# hiveScale.net
KiCad netlist of a schematic drawn in EAGLE
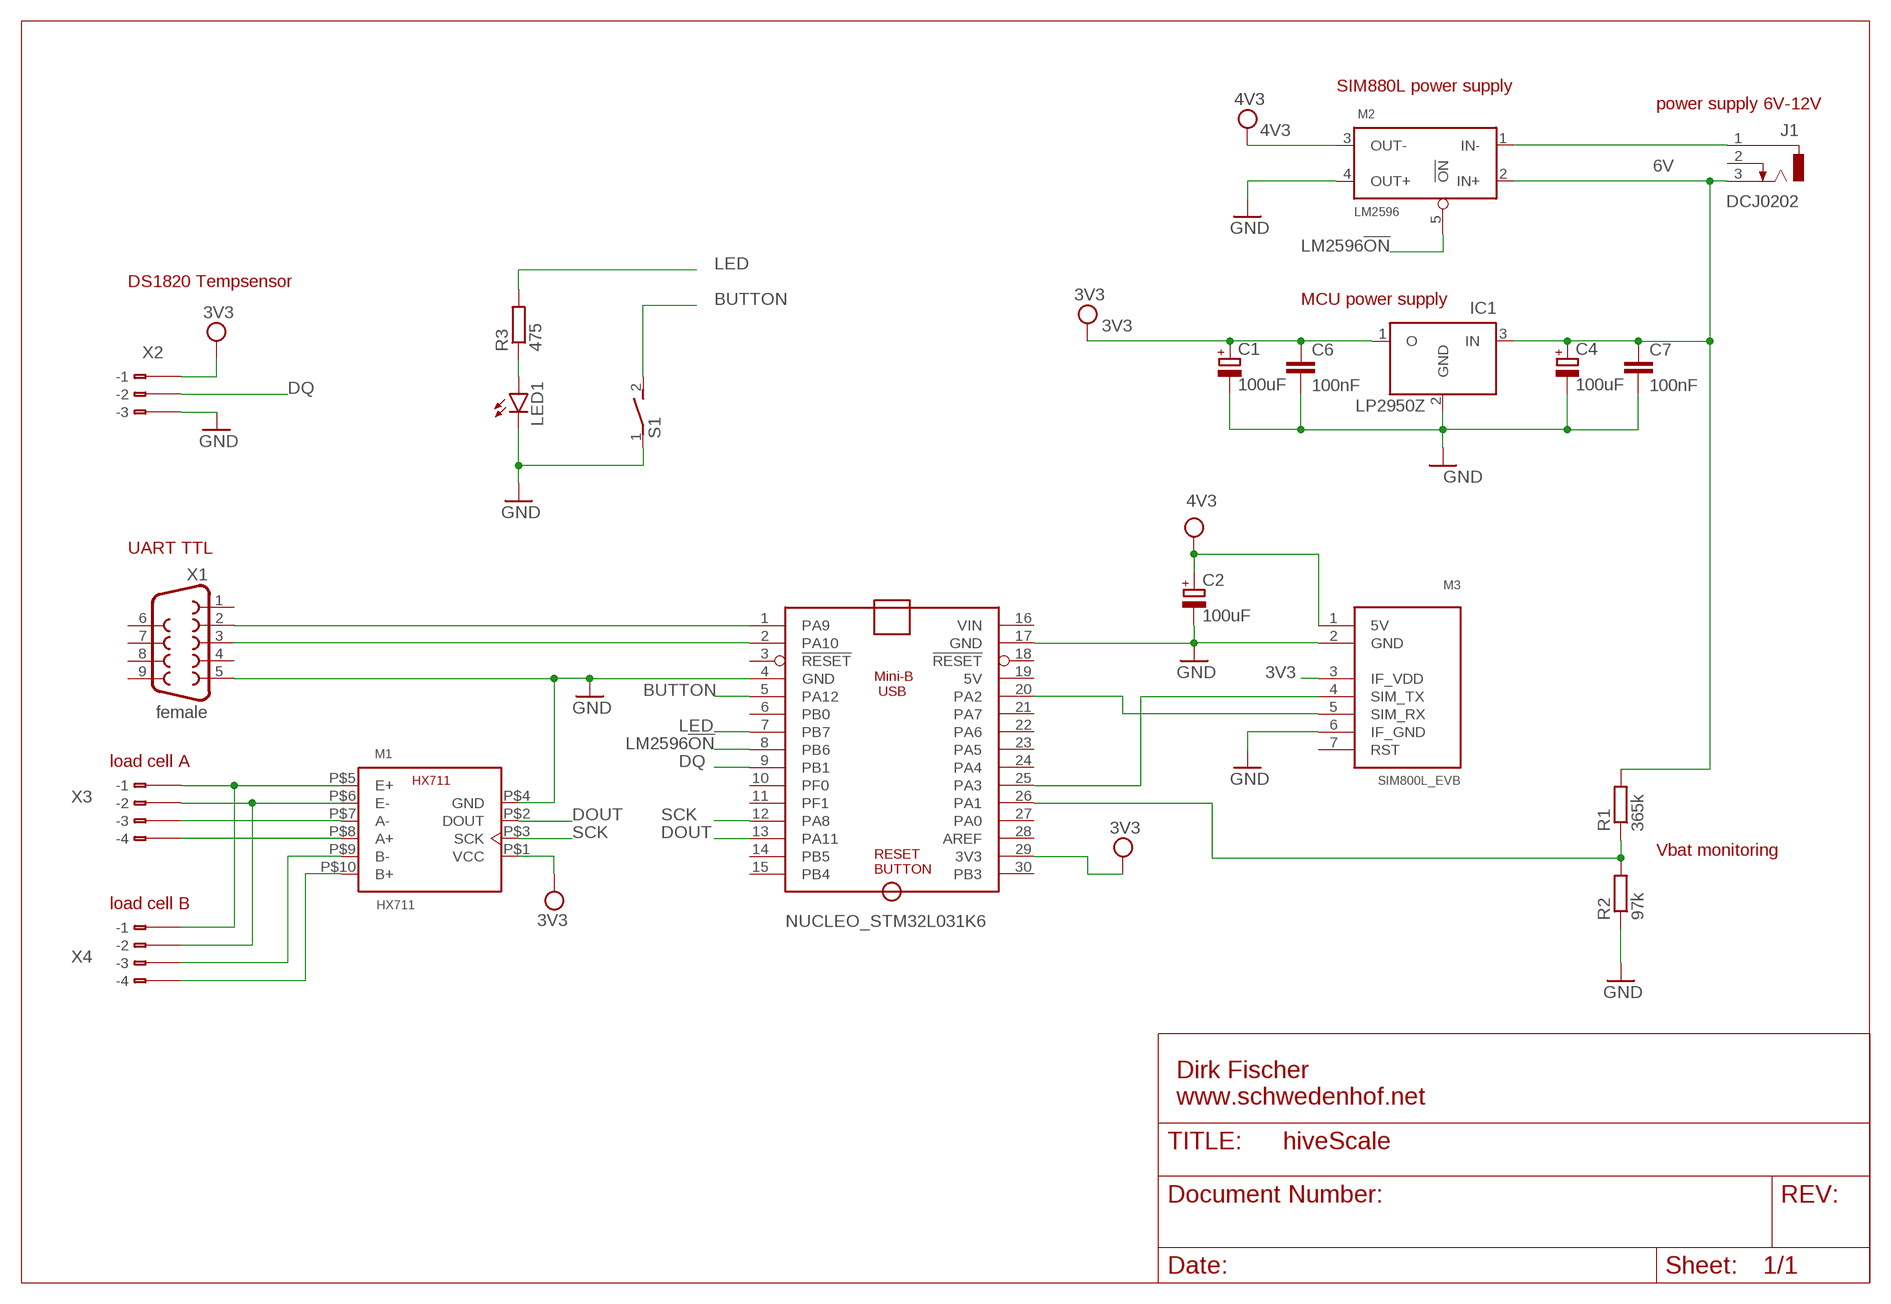
[diagram p0: schematic, sheet 1]

(export (version "E")
  (design (tool "Eeschema 10.0.6"))
  (components
    (comp (ref "C1")
      (value "100uF")
      (footprint "eagle-import:085CS_1AR")
      (libsource (lib "eagle-import") (part "CPOL-EU085CS-1AR"))
    )
    (comp (ref "C2")
      (value "100uF")
      (footprint "eagle-import:085CS_1AR")
      (libsource (lib "eagle-import") (part "CPOL-EU085CS-1AR"))
    )
    (comp (ref "C4")
      (value "100uF")
      (footprint "eagle-import:085CS_1AR")
      (libsource (lib "eagle-import") (part "CPOL-EU085CS-1AR"))
    )
    (comp (ref "C6")
      (value "100nF")
      (footprint "eagle-import:C025-024X044")
      (libsource (lib "eagle-import") (part "C-EU025-024X044"))
    )
    (comp (ref "C7")
      (value "100nF")
      (footprint "eagle-import:C025-024X044")
      (libsource (lib "eagle-import") (part "C-EU025-024X044"))
    )
    (comp (ref "IC1")
      (value "LP2950Z")
      (footprint "eagle-import:TO92")
      (fields (field (name "MF") "NATIONAL SEMICONDUCTOR") (field (name "MPN") "LP2950CZ-5.0/NOPB"))
      (libsource (lib "eagle-import") (part "LP2950Z"))
    )
    (comp (ref "J1")
      (value "DCJ0202")
      (footprint "eagle-import:DCJ0202")
      (libsource (lib "eagle-import") (part "DCJ0202"))
    )
    (comp (ref "LED1")
      (value "LED5MM")
      (footprint "eagle-import:LED5MM")
      (libsource (lib "eagle-import") (part "LED5MM"))
    )
    (comp (ref "M1")
      (value "HX711")
      (footprint "eagle-import:HX711")
      (libsource (lib "eagle-import") (part "HX711"))
    )
    (comp (ref "M2")
      (value "LM2596")
      (footprint "eagle-import:LM2596")
      (libsource (lib "eagle-import") (part "LM2596"))
    )
    (comp (ref "M3")
      (value "SIM800L_EVB")
      (footprint "eagle-import:SIM800L_EVB")
      (libsource (lib "eagle-import") (part "hiveScale_SIM800L_EVB"))
    )
    (comp (ref "NUCLEO_STM32L031K6")
      (value "ARDUINO_NANO")
      (footprint "eagle-import:ARDUINO_NANO")
      (libsource (lib "eagle-import") (part "ARDUINO_NANO"))
    )
    (comp (ref "R1")
      (value "365k")
      (footprint "eagle-import:0204_7")
      (libsource (lib "eagle-import") (part "R-EU_0204/7"))
    )
    (comp (ref "R2")
      (value "97k")
      (footprint "eagle-import:0204_7")
      (libsource (lib "eagle-import") (part "R-EU_0204/7"))
    )
    (comp (ref "R3")
      (value "475")
      (footprint "eagle-import:0204_7")
      (libsource (lib "eagle-import") (part "R-EU_0204/7"))
    )
    (comp (ref "S1")
      (value "DS01E")
      (footprint "eagle-import:DS-01")
      (libsource (lib "eagle-import") (part "DS01E"))
    )
    (comp (ref "X1")
      (value "female")
      (footprint "eagle-import:F09VP")
      (libsource (lib "eagle-import") (part "F09VP"))
    )
    (comp (ref "X2")
      (value "233-103")
      (footprint "eagle-import:233-103")
      (libsource (lib "eagle-import") (part "233-103"))
    )
    (comp (ref "X3")
      (value "233-104")
      (footprint "eagle-import:233-104")
      (libsource (lib "eagle-import") (part "233-104"))
    )
    (comp (ref "X4")
      (value "233-104")
      (footprint "eagle-import:233-104")
      (libsource (lib "eagle-import") (part "233-104"))
    )
  )
  (nets
    (net (code "1") (name "/5V") (class "Default")
      (node (ref "NUCLEO_STM32L031K6") (pin "19") (pinfunction "5V_19") (pintype "power_in"))
    )
    (net (code "2") (name "/6V") (class "Default")
      (node (ref "C4") (pin "+") (pinfunction "+_+") (pintype "passive"))
      (node (ref "C7") (pin "1") (pinfunction "1_1") (pintype "passive"))
      (node (ref "IC1") (pin "3") (pinfunction "IN_3") (pintype "input"))
      (node (ref "J1") (pin "3") (pinfunction "3_3") (pintype "passive"))
      (node (ref "M2") (pin "2") (pinfunction "IN+_2") (pintype "power_in"))
      (node (ref "R1") (pin "2") (pinfunction "2_2") (pintype "passive"))
    )
    (net (code "3") (name "/BUTTON") (class "Default")
      (node (ref "NUCLEO_STM32L031K6") (pin "5") (pinfunction "PA12_5") (pintype "bidirectional"))
      (node (ref "S1") (pin "2") (pinfunction "2_2") (pintype "passive"))
    )
    (net (code "4") (name "/DOUT") (class "Default")
      (node (ref "M1") (pin "P$2") (pinfunction "DOUT_P$2") (pintype "output"))
      (node (ref "NUCLEO_STM32L031K6") (pin "13") (pinfunction "PA11_13") (pintype "bidirectional"))
    )
    (net (code "5") (name "/DQ") (class "Default")
      (node (ref "NUCLEO_STM32L031K6") (pin "9") (pinfunction "PB1_9") (pintype "bidirectional"))
      (node (ref "X2") (pin "B2") (pinfunction "B-2_B2") (pintype "passive"))
    )
    (net (code "6") (name "/LED") (class "Default")
      (node (ref "NUCLEO_STM32L031K6") (pin "7") (pinfunction "PB7_7") (pintype "bidirectional"))
      (node (ref "R3") (pin "2") (pinfunction "2_2") (pintype "passive"))
    )
    (net (code "7") (name "/LM2596~{ON}") (class "Default")
      (node (ref "M2") (pin "5") (pinfunction "~{ON}_5") (pintype "input"))
      (node (ref "NUCLEO_STM32L031K6") (pin "8") (pinfunction "PB6_8") (pintype "bidirectional"))
    )
    (net (code "8") (name "/SCK") (class "Default")
      (node (ref "M1") (pin "P$3") (pinfunction "SCK_P$3") (pintype "input"))
      (node (ref "NUCLEO_STM32L031K6") (pin "12") (pinfunction "PA8_12") (pintype "bidirectional"))
    )
    (net (code "9") (name "/VIN") (class "Default")
      (node (ref "NUCLEO_STM32L031K6") (pin "16") (pinfunction "VIN_16") (pintype "power_in"))
    )
    (net (code "10") (name "3V3") (class "Default")
      (node (ref "C1") (pin "+") (pinfunction "+_+") (pintype "passive"))
      (node (ref "C6") (pin "1") (pinfunction "1_1") (pintype "passive"))
      (node (ref "IC1") (pin "1") (pinfunction "O_1") (pintype "output"))
      (node (ref "M1") (pin "P$1") (pinfunction "VCC_P$1") (pintype "power_in"))
      (node (ref "M3") (pin "3") (pinfunction "IF_VDD_3") (pintype "power_in"))
      (node (ref "NUCLEO_STM32L031K6") (pin "29") (pinfunction "3V3_29") (pintype "output"))
      (node (ref "X2") (pin "B1") (pinfunction "B-1_B1") (pintype "passive"))
    )
    (net (code "11") (name "4V3") (class "Default")
      (node (ref "C2") (pin "+") (pinfunction "+_+") (pintype "passive"))
      (node (ref "M2") (pin "3") (pinfunction "OUT-_3") (pintype "power_in"))
      (node (ref "M3") (pin "1") (pinfunction "5V_1") (pintype "power_in"))
    )
    (net (code "12") (name "GND") (class "Default")
      (node (ref "C1") (pin "-") (pinfunction "-_-") (pintype "passive"))
      (node (ref "C2") (pin "-") (pinfunction "-_-") (pintype "passive"))
      (node (ref "C4") (pin "-") (pinfunction "-_-") (pintype "passive"))
      (node (ref "C6") (pin "2") (pinfunction "2_2") (pintype "passive"))
      (node (ref "C7") (pin "2") (pinfunction "2_2") (pintype "passive"))
      (node (ref "IC1") (pin "2") (pinfunction "GND_2") (pintype "power_in"))
      (node (ref "LED1") (pin "K") (pinfunction "C_K") (pintype "passive"))
      (node (ref "M1") (pin "P$4") (pinfunction "GND_P$4") (pintype "power_in"))
      (node (ref "M2") (pin "4") (pinfunction "OUT+_4") (pintype "power_in"))
      (node (ref "M3") (pin "2") (pinfunction "GND_2") (pintype "power_in"))
      (node (ref "M3") (pin "6") (pinfunction "IF_GND_6") (pintype "power_in"))
      (node (ref "NUCLEO_STM32L031K6") (pin "17") (pinfunction "GND_17") (pintype "power_in"))
      (node (ref "NUCLEO_STM32L031K6") (pin "4") (pinfunction "GND_4") (pintype "power_in"))
      (node (ref "R2") (pin "1") (pinfunction "1_1") (pintype "passive"))
      (node (ref "S1") (pin "1") (pinfunction "1_1") (pintype "passive"))
      (node (ref "X1") (pin "5") (pinfunction "5_5") (pintype "passive"))
      (node (ref "X2") (pin "B3") (pinfunction "B-3_B3") (pintype "passive"))
    )
    (net (code "13") (name "Net-(LED1-PadA)") (class "Default")
      (node (ref "LED1") (pin "A") (pinfunction "A_A") (pintype "passive"))
      (node (ref "R3") (pin "1") (pinfunction "1_1") (pintype "passive"))
    )
    (net (code "14") (name "Net-(M1-A+)") (class "Default")
      (node (ref "M1") (pin "P$8") (pinfunction "A+_P$8") (pintype "bidirectional"))
      (node (ref "X3") (pin "B4") (pinfunction "B-4_B4") (pintype "passive"))
    )
    (net (code "15") (name "Net-(M1-A-)") (class "Default")
      (node (ref "M1") (pin "P$7") (pinfunction "A-_P$7") (pintype "bidirectional"))
      (node (ref "X3") (pin "B3") (pinfunction "B-3_B3") (pintype "passive"))
    )
    (net (code "16") (name "Net-(M1-B+)") (class "Default")
      (node (ref "M1") (pin "P$10") (pinfunction "B+_P$10") (pintype "bidirectional"))
      (node (ref "X4") (pin "B4") (pinfunction "B-4_B4") (pintype "passive"))
    )
    (net (code "17") (name "Net-(M1-B-)") (class "Default")
      (node (ref "M1") (pin "P$9") (pinfunction "B-_P$9") (pintype "bidirectional"))
      (node (ref "X4") (pin "B3") (pinfunction "B-3_B3") (pintype "passive"))
    )
    (net (code "18") (name "Net-(M1-E+)") (class "Default")
      (node (ref "M1") (pin "P$5") (pinfunction "E+_P$5") (pintype "power_in"))
      (node (ref "X3") (pin "B1") (pinfunction "B-1_B1") (pintype "passive"))
      (node (ref "X4") (pin "B1") (pinfunction "B-1_B1") (pintype "passive"))
    )
    (net (code "19") (name "Net-(M1-E-)") (class "Default")
      (node (ref "M1") (pin "P$6") (pinfunction "E-_P$6") (pintype "power_in"))
      (node (ref "X3") (pin "B2") (pinfunction "B-2_B2") (pintype "passive"))
      (node (ref "X4") (pin "B2") (pinfunction "B-2_B2") (pintype "passive"))
    )
    (net (code "20") (name "Net-(M2-IN-)") (class "Default")
      (node (ref "J1") (pin "1") (pinfunction "1_1") (pintype "passive"))
      (node (ref "M2") (pin "1") (pinfunction "IN-_1") (pintype "power_in"))
    )
    (net (code "21") (name "Net-(M3-SIM_RX)") (class "Default")
      (node (ref "M3") (pin "5") (pinfunction "SIM_RX_5") (pintype "input"))
      (node (ref "NUCLEO_STM32L031K6") (pin "20") (pinfunction "PA2_20") (pintype "bidirectional"))
    )
    (net (code "22") (name "Net-(M3-SIM_TX)") (class "Default")
      (node (ref "M3") (pin "4") (pinfunction "SIM_TX_4") (pintype "output"))
      (node (ref "NUCLEO_STM32L031K6") (pin "25") (pinfunction "PA3_25") (pintype "bidirectional"))
    )
    (net (code "23") (name "Net-(NUCLEO_STM32L031K6-PA1)") (class "Default")
      (node (ref "NUCLEO_STM32L031K6") (pin "26") (pinfunction "PA1_26") (pintype "bidirectional"))
      (node (ref "R1") (pin "1") (pinfunction "1_1") (pintype "passive"))
      (node (ref "R2") (pin "2") (pinfunction "2_2") (pintype "passive"))
    )
    (net (code "24") (name "Net-(NUCLEO_STM32L031K6-PA9)") (class "Default")
      (node (ref "NUCLEO_STM32L031K6") (pin "1") (pinfunction "PA9_1") (pintype "bidirectional"))
      (node (ref "X1") (pin "2") (pinfunction "2_2") (pintype "passive"))
    )
    (net (code "25") (name "Net-(NUCLEO_STM32L031K6-PA10)") (class "Default")
      (node (ref "NUCLEO_STM32L031K6") (pin "2") (pinfunction "PA10_2") (pintype "bidirectional"))
      (node (ref "X1") (pin "3") (pinfunction "3_3") (pintype "passive"))
    )
    (net (code "26") (name "unconnected-(J1-Pad2)") (class "Default")
      (node (ref "J1") (pin "2") (pinfunction "2_2") (pintype "passive"))
    )
    (net (code "27") (name "unconnected-(M3-RST-Pad7)") (class "Default")
      (node (ref "M3") (pin "7") (pinfunction "RST_7") (pintype "input"))
    )
    (net (code "28") (name "unconnected-(NUCLEO_STM32L031K6-AREF-Pad28)") (class "Default")
      (node (ref "NUCLEO_STM32L031K6") (pin "28") (pinfunction "AREF_28") (pintype "input"))
    )
    (net (code "29") (name "unconnected-(NUCLEO_STM32L031K6-PA0-Pad27)") (class "Default")
      (node (ref "NUCLEO_STM32L031K6") (pin "27") (pinfunction "PA0_27") (pintype "bidirectional"))
    )
    (net (code "30") (name "unconnected-(NUCLEO_STM32L031K6-PA4-Pad24)") (class "Default")
      (node (ref "NUCLEO_STM32L031K6") (pin "24") (pinfunction "PA4_24") (pintype "bidirectional"))
    )
    (net (code "31") (name "unconnected-(NUCLEO_STM32L031K6-PA5-Pad23)") (class "Default")
      (node (ref "NUCLEO_STM32L031K6") (pin "23") (pinfunction "PA5_23") (pintype "bidirectional"))
    )
    (net (code "32") (name "unconnected-(NUCLEO_STM32L031K6-PA6-Pad22)") (class "Default")
      (node (ref "NUCLEO_STM32L031K6") (pin "22") (pinfunction "PA6_22") (pintype "bidirectional"))
    )
    (net (code "33") (name "unconnected-(NUCLEO_STM32L031K6-PA7-Pad21)") (class "Default")
      (node (ref "NUCLEO_STM32L031K6") (pin "21") (pinfunction "PA7_21") (pintype "bidirectional"))
    )
    (net (code "34") (name "unconnected-(NUCLEO_STM32L031K6-PB0-Pad6)") (class "Default")
      (node (ref "NUCLEO_STM32L031K6") (pin "6") (pinfunction "PB0_6") (pintype "bidirectional"))
    )
    (net (code "35") (name "unconnected-(NUCLEO_STM32L031K6-PB3-Pad30)") (class "Default")
      (node (ref "NUCLEO_STM32L031K6") (pin "30") (pinfunction "PB3_30") (pintype "bidirectional"))
    )
    (net (code "36") (name "unconnected-(NUCLEO_STM32L031K6-PB4-Pad15)") (class "Default")
      (node (ref "NUCLEO_STM32L031K6") (pin "15") (pinfunction "PB4_15") (pintype "bidirectional"))
    )
    (net (code "37") (name "unconnected-(NUCLEO_STM32L031K6-PB5-Pad14)") (class "Default")
      (node (ref "NUCLEO_STM32L031K6") (pin "14") (pinfunction "PB5_14") (pintype "bidirectional"))
    )
    (net (code "38") (name "unconnected-(NUCLEO_STM32L031K6-PF0-Pad10)") (class "Default")
      (node (ref "NUCLEO_STM32L031K6") (pin "10") (pinfunction "PF0_10") (pintype "bidirectional"))
    )
    (net (code "39") (name "unconnected-(NUCLEO_STM32L031K6-PF1-Pad11)") (class "Default")
      (node (ref "NUCLEO_STM32L031K6") (pin "11") (pinfunction "PF1_11") (pintype "bidirectional"))
    )
    (net (code "40") (name "unconnected-(NUCLEO_STM32L031K6-~{RESET}-Pad3)") (class "Default")
      (node (ref "NUCLEO_STM32L031K6") (pin "3") (pinfunction "~{RESET}_3") (pintype "input"))
    )
    (net (code "41") (name "unconnected-(NUCLEO_STM32L031K6-~{RESET}-Pad18)") (class "Default")
      (node (ref "NUCLEO_STM32L031K6") (pin "18") (pinfunction "~{RESET}_18") (pintype "input"))
    )
    (net (code "42") (name "unconnected-(X1-Pad1)") (class "Default")
      (node (ref "X1") (pin "1") (pinfunction "1_1") (pintype "passive"))
    )
    (net (code "43") (name "unconnected-(X1-Pad4)") (class "Default")
      (node (ref "X1") (pin "4") (pinfunction "4_4") (pintype "passive"))
    )
    (net (code "44") (name "unconnected-(X1-Pad6)") (class "Default")
      (node (ref "X1") (pin "6") (pinfunction "6_6") (pintype "passive"))
    )
    (net (code "45") (name "unconnected-(X1-Pad7)") (class "Default")
      (node (ref "X1") (pin "7") (pinfunction "7_7") (pintype "passive"))
    )
    (net (code "46") (name "unconnected-(X1-Pad8)") (class "Default")
      (node (ref "X1") (pin "8") (pinfunction "8_8") (pintype "passive"))
    )
    (net (code "47") (name "unconnected-(X1-Pad9)") (class "Default")
      (node (ref "X1") (pin "9") (pinfunction "9_9") (pintype "passive"))
    )
    (net (code "48") (name "unconnected-(X2--1-PadA1)") (class "Default")
      (node (ref "X2") (pin "A1") (pinfunction "-1_A1") (pintype "passive"))
    )
    (net (code "49") (name "unconnected-(X2--2-PadA2)") (class "Default")
      (node (ref "X2") (pin "A2") (pinfunction "-2_A2") (pintype "passive"))
    )
    (net (code "50") (name "unconnected-(X2--3-PadA3)") (class "Default")
      (node (ref "X2") (pin "A3") (pinfunction "-3_A3") (pintype "passive"))
    )
    (net (code "51") (name "unconnected-(X3--1-PadA1)") (class "Default")
      (node (ref "X3") (pin "A1") (pinfunction "-1_A1") (pintype "passive"))
    )
    (net (code "52") (name "unconnected-(X3--2-PadA2)") (class "Default")
      (node (ref "X3") (pin "A2") (pinfunction "-2_A2") (pintype "passive"))
    )
    (net (code "53") (name "unconnected-(X3--3-PadA3)") (class "Default")
      (node (ref "X3") (pin "A3") (pinfunction "-3_A3") (pintype "passive"))
    )
    (net (code "54") (name "unconnected-(X3--4-PadA4)") (class "Default")
      (node (ref "X3") (pin "A4") (pinfunction "-4_A4") (pintype "passive"))
    )
    (net (code "55") (name "unconnected-(X4--1-PadA1)") (class "Default")
      (node (ref "X4") (pin "A1") (pinfunction "-1_A1") (pintype "passive"))
    )
    (net (code "56") (name "unconnected-(X4--2-PadA2)") (class "Default")
      (node (ref "X4") (pin "A2") (pinfunction "-2_A2") (pintype "passive"))
    )
    (net (code "57") (name "unconnected-(X4--3-PadA3)") (class "Default")
      (node (ref "X4") (pin "A3") (pinfunction "-3_A3") (pintype "passive"))
    )
    (net (code "58") (name "unconnected-(X4--4-PadA4)") (class "Default")
      (node (ref "X4") (pin "A4") (pinfunction "-4_A4") (pintype "passive"))
    )
  )
)
